# 11_HDMI_CON.net
KiCad netlist of a schematic drawn in Altium Designer
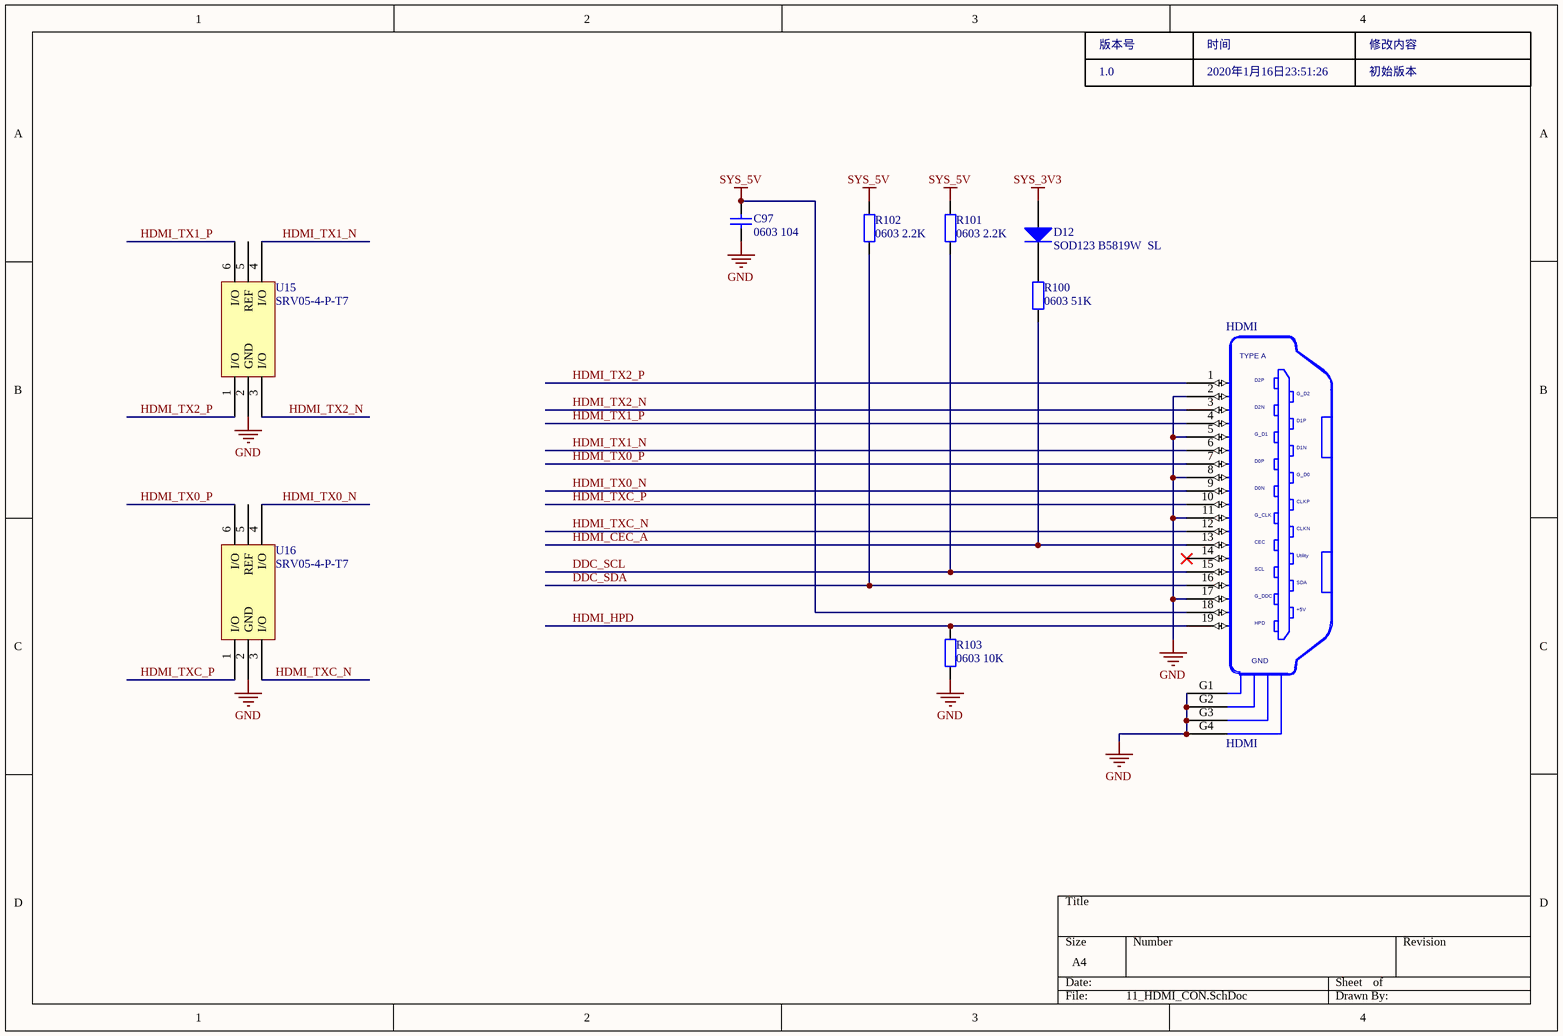
[diagram p0: 11_HDMI_CON.SchDoc]

(export (version "E")
  (design (tool "Eeschema 10.0.6"))
  (components
    (comp (ref "C97")
      (value "0603 104")
      (footprint "LC-0603_C")
      (description "贴片电容")
      (libsource (lib "JLC") (part "0603 1.5nF (152) 10% 50V"))
    )
    (comp (ref "D12")
      (value "SOD123 B5819W  SL")
      (footprint "LC-SOD-123")
      (description "肖特基二极管")
      (libsource (lib "JLC") (part "SOD-123 B5819W  SL"))
    )
    (comp (ref "HDMI")
      (value "HDMI")
      (footprint "HDMI")
      (libsource (lib "Integrated_Library2") (part "HDMI"))
    )
    (comp (ref "R100")
      (value "0603 51K")
      (footprint "LC-0603_R")
      (description "贴片电阻")
      (libsource (lib "JLC") (part "0603 1.1KΩ (1101) 1%"))
    )
    (comp (ref "R101")
      (value "0603 2.2K")
      (footprint "LC-0603_R")
      (description "贴片电阻")
      (libsource (lib "JLC") (part "0603 1.1KΩ (1101) 1%"))
    )
    (comp (ref "R102")
      (value "0603 2.2K")
      (footprint "LC-0603_R")
      (description "贴片电阻")
      (libsource (lib "JLC") (part "0603 1.1KΩ (1101) 1%"))
    )
    (comp (ref "R103")
      (value "0603 10K")
      (footprint "LC-0603_R")
      (description "贴片电阻")
      (libsource (lib "JLC") (part "0603 1.1KΩ (1101) 1%"))
    )
    (comp (ref "U15")
      (value "SRV05-4-P-T7")
      (footprint "LC-SOT-23-6")
      (description "TVS")
      (libsource (lib "JLC") (part "SRV05-4-P-T7"))
    )
    (comp (ref "U16")
      (value "SRV05-4-P-T7")
      (footprint "LC-SOT-23-6")
      (description "TVS")
      (libsource (lib "JLC") (part "SRV05-4-P-T7"))
    )
  )
  (nets
    (net (code "1") (name "/DDC_SCL") (class "Default")
      (node (ref "HDMI") (pin "15") (pinfunction "SCL_15") (pintype "bidirectional"))
      (node (ref "R101") (pin "1") (pinfunction "1_1") (pintype "passive"))
    )
    (net (code "2") (name "/DDC_SDA") (class "Default")
      (node (ref "HDMI") (pin "16") (pinfunction "SDA_16") (pintype "bidirectional"))
      (node (ref "R102") (pin "1") (pinfunction "1_1") (pintype "passive"))
    )
    (net (code "3") (name "/HDMI_CEC_A") (class "Default")
      (node (ref "HDMI") (pin "13") (pinfunction "CEC_13") (pintype "bidirectional"))
      (node (ref "R100") (pin "1") (pinfunction "1_1") (pintype "passive"))
    )
    (net (code "4") (name "/HDMI_HPD") (class "Default")
      (node (ref "HDMI") (pin "19") (pinfunction "HPD_19") (pintype "bidirectional"))
      (node (ref "R103") (pin "2") (pinfunction "2_2") (pintype "passive"))
    )
    (net (code "5") (name "/HDMI_TX0_N") (class "Default")
      (node (ref "HDMI") (pin "9") (pinfunction "D0-_9") (pintype "bidirectional"))
      (node (ref "U16") (pin "4") (pinfunction "I/O_4") (pintype "passive"))
    )
    (net (code "6") (name "/HDMI_TX0_P") (class "Default")
      (node (ref "HDMI") (pin "7") (pinfunction "D0+_7") (pintype "bidirectional"))
      (node (ref "U16") (pin "6") (pinfunction "I/O_6") (pintype "passive"))
    )
    (net (code "7") (name "/HDMI_TX1_N") (class "Default")
      (node (ref "HDMI") (pin "6") (pinfunction "D1-_6") (pintype "bidirectional"))
      (node (ref "U15") (pin "4") (pinfunction "I/O_4") (pintype "passive"))
    )
    (net (code "8") (name "/HDMI_TX1_P") (class "Default")
      (node (ref "HDMI") (pin "4") (pinfunction "D1+_4") (pintype "bidirectional"))
      (node (ref "U15") (pin "6") (pinfunction "I/O_6") (pintype "passive"))
    )
    (net (code "9") (name "/HDMI_TX2_N") (class "Default")
      (node (ref "HDMI") (pin "3") (pinfunction "D2-_3") (pintype "bidirectional"))
      (node (ref "U15") (pin "3") (pinfunction "I/O_3") (pintype "passive"))
    )
    (net (code "10") (name "/HDMI_TX2_P") (class "Default")
      (node (ref "HDMI") (pin "1") (pinfunction "D2+_1") (pintype "bidirectional"))
      (node (ref "U15") (pin "1") (pinfunction "I/O_1") (pintype "passive"))
    )
    (net (code "11") (name "/HDMI_TXC_N") (class "Default")
      (node (ref "HDMI") (pin "12") (pinfunction "CK-_12") (pintype "bidirectional"))
      (node (ref "U16") (pin "3") (pinfunction "I/O_3") (pintype "passive"))
    )
    (net (code "12") (name "/HDMI_TXC_P") (class "Default")
      (node (ref "HDMI") (pin "10") (pinfunction "CK+_10") (pintype "bidirectional"))
      (node (ref "U16") (pin "1") (pinfunction "I/O_1") (pintype "passive"))
    )
    (net (code "13") (name "GND") (class "Default")
      (node (ref "C97") (pin "2") (pinfunction "2_2") (pintype "passive"))
      (node (ref "HDMI") (pin "11") (pinfunction "CKGND_11") (pintype "bidirectional"))
      (node (ref "HDMI") (pin "17") (pinfunction "DDCGND_17") (pintype "bidirectional"))
      (node (ref "HDMI") (pin "2") (pinfunction "D2GND_2") (pintype "bidirectional"))
      (node (ref "HDMI") (pin "5") (pinfunction "D1GND_5") (pintype "bidirectional"))
      (node (ref "HDMI") (pin "8") (pinfunction "D0GND_8") (pintype "bidirectional"))
      (node (ref "HDMI") (pin "G1") (pinfunction "GND1_G1") (pintype "power_in"))
      (node (ref "HDMI") (pin "G2") (pinfunction "GND2_G2") (pintype "power_in"))
      (node (ref "HDMI") (pin "G3") (pinfunction "GND3_G3") (pintype "power_in"))
      (node (ref "HDMI") (pin "G4") (pinfunction "GND4_G4") (pintype "power_in"))
      (node (ref "R103") (pin "1") (pinfunction "1_1") (pintype "passive"))
      (node (ref "U15") (pin "2") (pinfunction "GND_2") (pintype "passive"))
      (node (ref "U16") (pin "2") (pinfunction "GND_2") (pintype "passive"))
    )
    (net (code "14") (name "Net-(D12-K)") (class "Default")
      (node (ref "D12") (pin "2") (pinfunction "K_2") (pintype "passive"))
      (node (ref "R100") (pin "2") (pinfunction "2_2") (pintype "passive"))
    )
    (net (code "15") (name "SYS_3V3") (class "Default")
      (node (ref "D12") (pin "1") (pinfunction "A_1") (pintype "passive"))
    )
    (net (code "16") (name "SYS_5V") (class "Default")
      (node (ref "C97") (pin "1") (pinfunction "1_1") (pintype "passive"))
      (node (ref "HDMI") (pin "18") (pinfunction "+5V_18") (pintype "bidirectional"))
      (node (ref "R101") (pin "2") (pinfunction "2_2") (pintype "passive"))
      (node (ref "R102") (pin "2") (pinfunction "2_2") (pintype "passive"))
    )
    (net (code "17") (name "unconnected-(HDMI-UTILITY-Pad14)") (class "Default")
      (node (ref "HDMI") (pin "14") (pinfunction "UTILITY_14") (pintype "bidirectional+no_connect"))
    )
    (net (code "18") (name "unconnected-(U15-REF-Pad5)") (class "Default")
      (node (ref "U15") (pin "5") (pinfunction "REF_5") (pintype "passive"))
    )
    (net (code "19") (name "unconnected-(U16-REF-Pad5)") (class "Default")
      (node (ref "U16") (pin "5") (pinfunction "REF_5") (pintype "passive"))
    )
  )
)
